# SOC_PMU_Controller.net
KiCad netlist of a schematic drawn in Altium Designer
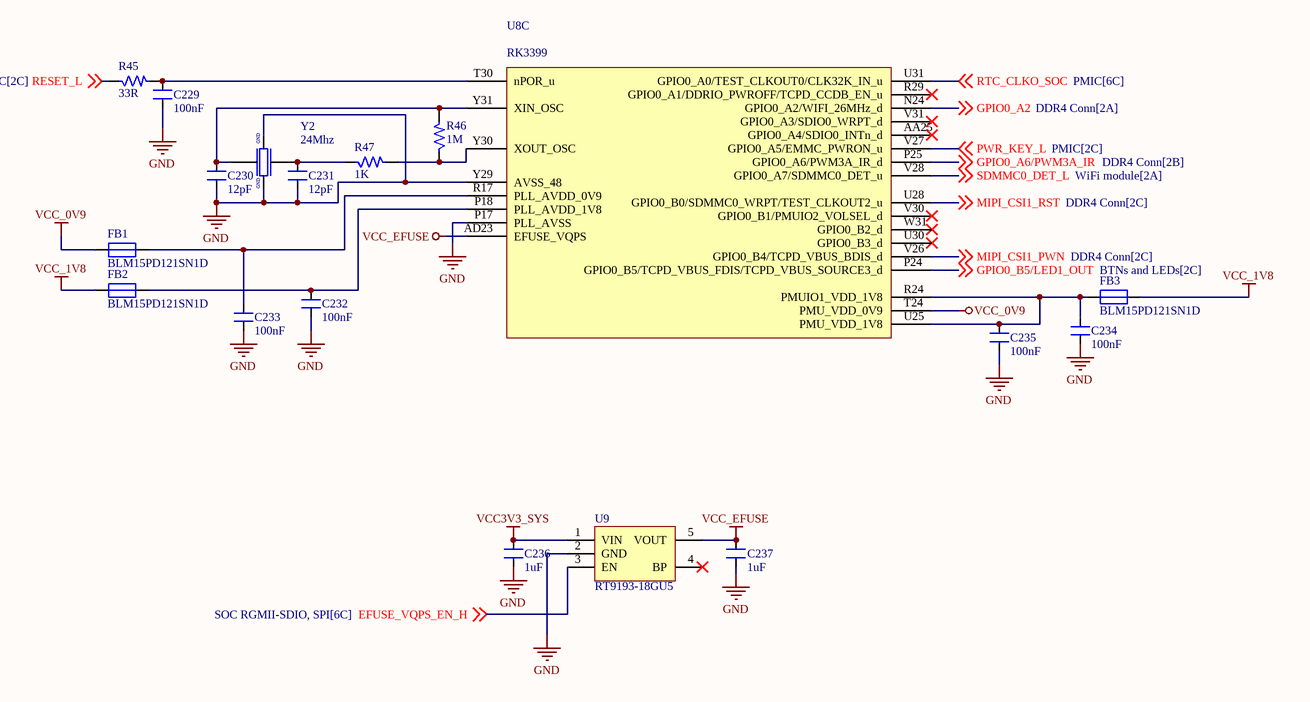
[diagram p0: SOC PMU Controller.SchDoc]

(export (version "E")
  (design (tool "Eeschema 10.0.6"))
  (components
    (comp (ref "C229")
      (value "100nF")
      (footprint "CAP_0201")
      (description "0.1µF ±10% 25V Ceramic Capacitor X5R 0201 (0603 Metric)")
      (fields
        (field (name "MANUFACTURER") "TDK Corporation")
        (field (name "MANUFACTURER PART NUMBER") "C0603X5R1E104K030BB")
      )
      (libsource (lib "RK3399 _Module_Intlib") (part "CAP_100nF-25V-10%-0201"))
    )
    (comp (ref "C230")
      (value "12pF")
      (footprint "CAP_0201")
      (description "12pF ±10% 16V Ceramic Capacitor C0G, NP0 0201 (0603 Metric)")
      (fields
        (field (name "MANUFACTURER") "AVX Corporation")
        (field (name "MANUFACTURER PART NUMBER") "0201YA120KAT2A")
      )
      (libsource (lib "RK3399 _Module_Intlib") (part "CAP_12pF-16V-10%-0201"))
    )
    (comp (ref "C231")
      (value "12pF")
      (footprint "CAP_0201")
      (description "12pF ±10% 16V Ceramic Capacitor C0G, NP0 0201 (0603 Metric)")
      (fields
        (field (name "MANUFACTURER") "AVX Corporation")
        (field (name "MANUFACTURER PART NUMBER") "0201YA120KAT2A")
      )
      (libsource (lib "RK3399 _Module_Intlib") (part "CAP_12pF-16V-10%-0201"))
    )
    (comp (ref "C232")
      (value "100nF")
      (footprint "CAP_0201")
      (description "0.1µF ±10% 25V Ceramic Capacitor X5R 0201 (0603 Metric)")
      (fields
        (field (name "MANUFACTURER") "TDK Corporation")
        (field (name "MANUFACTURER PART NUMBER") "C0603X5R1E104K030BB")
      )
      (libsource (lib "RK3399 _Module_Intlib") (part "CAP_100nF-25V-10%-0201"))
    )
    (comp (ref "C233")
      (value "100nF")
      (footprint "CAP_0201")
      (description "0.1µF ±10% 25V Ceramic Capacitor X5R 0201 (0603 Metric)")
      (fields
        (field (name "MANUFACTURER") "TDK Corporation")
        (field (name "MANUFACTURER PART NUMBER") "C0603X5R1E104K030BB")
      )
      (libsource (lib "RK3399 _Module_Intlib") (part "CAP_100nF-25V-10%-0201"))
    )
    (comp (ref "C234")
      (value "100nF")
      (footprint "CAP_0201")
      (description "0.1µF ±10% 25V Ceramic Capacitor X5R 0201 (0603 Metric)")
      (fields
        (field (name "MANUFACTURER") "TDK Corporation")
        (field (name "MANUFACTURER PART NUMBER") "C0603X5R1E104K030BB")
      )
      (libsource (lib "RK3399 _Module_Intlib") (part "CAP_100nF-25V-10%-0201"))
    )
    (comp (ref "C235")
      (value "100nF")
      (footprint "CAP_0201")
      (description "0.1µF ±10% 25V Ceramic Capacitor X5R 0201 (0603 Metric)")
      (fields
        (field (name "MANUFACTURER") "TDK Corporation")
        (field (name "MANUFACTURER PART NUMBER") "C0603X5R1E104K030BB")
      )
      (libsource (lib "RK3399 _Module_Intlib") (part "CAP_100nF-25V-10%-0201"))
    )
    (comp (ref "C236")
      (value "1uF")
      (footprint "CAP_0201")
      (description "1µF ±20% 16V Ceramic Capacitor X5R 0201 (0603 Metric)")
      (fields
        (field (name "MANUFACTURER") "Samsung Electro-Mechanics")
        (field (name "MANUFACTURER PART NUMBER") "CL03A105MO3NRNH")
      )
      (libsource (lib "RK3399 _Module_Intlib") (part "CAP_1uF-16V-10%-0201"))
    )
    (comp (ref "C237")
      (value "1uF")
      (footprint "CAP_0201")
      (description "1µF ±20% 16V Ceramic Capacitor X5R 0201 (0603 Metric)")
      (fields
        (field (name "MANUFACTURER") "Samsung Electro-Mechanics")
        (field (name "MANUFACTURER PART NUMBER") "CL03A105MO3NRNH")
      )
      (libsource (lib "RK3399 _Module_Intlib") (part "CAP_1uF-16V-10%-0201"))
    )
    (comp (ref "FB1")
      (value "BLM15PD121SN1D")
      (footprint "RES_0402")
      (description "120 Ohms @ 100MHz 1 Power Line Ferrite Bead 0402 (1005 Metric) 1.3A 90mOhm")
      (fields (field (name "MANUFACTURER") "Murata Electronics"))
      (libsource (lib "RK3399 _Module_Schlib") (part "FB_120R-1.3A-100Mhz-0402"))
    )
    (comp (ref "FB2")
      (value "BLM15PD121SN1D")
      (footprint "RES_0402")
      (description "120 Ohms @ 100MHz 1 Power Line Ferrite Bead 0402 (1005 Metric) 1.3A 90mOhm")
      (fields (field (name "MANUFACTURER") "Murata Electronics"))
      (libsource (lib "RK3399 _Module_Schlib") (part "FB_120R-1.3A-100Mhz-0402"))
    )
    (comp (ref "FB3")
      (value "BLM15PD121SN1D")
      (footprint "RES_0402")
      (description "120 Ohms @ 100MHz 1 Power Line Ferrite Bead 0402 (1005 Metric) 1.3A 90mOhm")
      (fields (field (name "MANUFACTURER") "Murata Electronics"))
      (libsource (lib "RK3399 _Module_Schlib") (part "FB_120R-1.3A-100Mhz-0402"))
    )
    (comp (ref "R45")
      (value "33R")
      (footprint "RES_0201")
      (description "33 Ohms ±1% 0.05W, 1/20W Chip Resistor 0201 (0603 Metric) Thick Film")
      (fields
        (field (name "MANUFACTURER") "Yageo")
        (field (name "MANUFACTURER PART NUMBER") "RC0201FR-0733RL")
      )
      (libsource (lib "RK3399 _Module_Intlib") (part "RES_33R-0.05W-1%-0201"))
    )
    (comp (ref "R46")
      (value "1M")
      (footprint "RES_0201")
      (description "1 MOhms ±1% 0.05W, 1/20W Chip Resistor 0201 (0603 Metric) Thick Film")
      (fields
        (field (name "MANUFACTURER") "Yageo")
        (field (name "MANUFACTURER PART NUMBER") "RC0201FR-071ML")
      )
      (libsource (lib "RK3399 _Module_Intlib") (part "RES_1M-0.05W-1%-0201"))
    )
    (comp (ref "R47")
      (value "1K")
      (footprint "RES_0201")
      (description "1 kOhms ±1% 0.05W, 1/20W Chip Resistor 0201 (0603 Metric) Thick Film")
      (fields
        (field (name "MANUFACTURER") "Yageo")
        (field (name "MANUFACTURER PART NUMBER") "RC0201FR-071KL")
      )
      (libsource (lib "RK3399 _Module_Intlib") (part "RES_1K-0.05W-1%-0201"))
    )
    (comp (ref "U8")
      (value "RK3399")
      (footprint "FBGA828_23_826X826")
      (description "RK3399 is a low power, high performance processor for computing, personal mobile.")
      (fields (field (name "MANUFACTURER") "Rockchip"))
      (libsource (lib "RK3399 _Module_Schlib") (part "IC_RK3399-FCBGA828"))
    )
    (comp (ref "U9")
      (value "RT9193-18GU5")
      (footprint "SC70-5")
      (description "Linear Voltage Regulator IC 1 Output 300mA SC-70-5")
      (fields (field (name "MANUFACTURER") "Richtek USA Inc."))
      (libsource (lib "RK3399 _Module_Schlib") (part "REG_1.8V-300mA-5.5V-SC70-5"))
    )
    (comp (ref "Y2")
      (value "24Mhz")
      (footprint "XTAL_ABM8AIG-24.000MHZ-12-2Z-T3")
      (description "24MHz ±20ppm Crystal 12pF 50 Ohms 4-SMD, No Lead")
      (fields
        (field (name "MANUFACTURER") "Abracon LLC")
        (field (name "MANUFACTURER PART NUMBER") "ABM8AIG-24.000MHZ-12-2Z-T3")
      )
      (libsource (lib "RK3399 _Module_Schlib") (part "XTAL_24Mhz-12pF-4-SMD"))
    )
  )
  (nets
    (net (code "1") (name "EFUSE_VQPS_EN_H") (class "Default")
      (node (ref "U9") (pin "3") (pinfunction "EN_3") (pintype "passive"))
    )
    (net (code "2") (name "GND") (class "Default")
      (node (ref "C229") (pin "1") (pinfunction "1_1") (pintype "passive"))
      (node (ref "C230") (pin "1") (pinfunction "1_1") (pintype "passive"))
      (node (ref "C231") (pin "1") (pinfunction "1_1") (pintype "passive"))
      (node (ref "C232") (pin "1") (pinfunction "1_1") (pintype "passive"))
      (node (ref "C233") (pin "1") (pinfunction "1_1") (pintype "passive"))
      (node (ref "C234") (pin "1") (pinfunction "1_1") (pintype "passive"))
      (node (ref "C235") (pin "1") (pinfunction "1_1") (pintype "passive"))
      (node (ref "C236") (pin "1") (pinfunction "1_1") (pintype "passive"))
      (node (ref "C237") (pin "1") (pinfunction "1_1") (pintype "passive"))
      (node (ref "U8") (pin "P17") (pinfunction "PLL_AVSS_P17") (pintype "passive"))
      (node (ref "U8") (pin "Y29") (pinfunction "AVSS_48_Y29") (pintype "passive"))
      (node (ref "U9") (pin "2") (pinfunction "GND_2") (pintype "passive"))
      (node (ref "Y2") (pin "2") (pinfunction "2_2") (pintype "passive"))
      (node (ref "Y2") (pin "4") (pinfunction "4_4") (pintype "passive"))
    )
    (net (code "3") (name "GPIO0_A2") (class "Default")
      (node (ref "U8") (pin "N24") (pinfunction "GPIO0_A2/WIFI_26MHz_d_N24") (pintype "passive"))
    )
    (net (code "4") (name "GPIO0_A6{slash}PWM3A_IR") (class "Default")
      (node (ref "U8") (pin "P25") (pinfunction "GPIO0_A6/PWM3A_IR_d_P25") (pintype "passive"))
    )
    (net (code "5") (name "GPIO0_B5{slash}LED1_OUT") (class "Default")
      (node (ref "U8") (pin "P24") (pinfunction "GPIO0_B5/TCPD_VBUS_FDIS/TCPD_VBUS_SOURCE3_d_P24") (pintype "passive"))
    )
    (net (code "6") (name "MIPI_CSI1_PWN") (class "Default")
      (node (ref "U8") (pin "V26") (pinfunction "GPIO0_B4/TCPD_VBUS_BDIS_d_V26") (pintype "passive"))
    )
    (net (code "7") (name "MIPI_CSI1_RST") (class "Default")
      (node (ref "U8") (pin "U28") (pinfunction "GPIO0_B0/SDMMC0_WRPT/TEST_CLKOUT2_u_U28") (pintype "passive"))
    )
    (net (code "8") (name "Net-(C231-Pad2)") (class "Default")
      (node (ref "C231") (pin "2") (pinfunction "2_2") (pintype "passive"))
      (node (ref "R47") (pin "1") (pinfunction "1_1") (pintype "passive"))
      (node (ref "Y2") (pin "3") (pinfunction "3_3") (pintype "passive"))
    )
    (net (code "9") (name "Net-(U8C-PLL_AVDD_0V9)") (class "Default")
      (node (ref "C233") (pin "2") (pinfunction "2_2") (pintype "passive"))
      (node (ref "FB1") (pin "2") (pinfunction "2_2") (pintype "passive"))
      (node (ref "U8") (pin "R17") (pinfunction "PLL_AVDD_0V9_R17") (pintype "passive"))
    )
    (net (code "10") (name "Net-(U8C-PLL_AVDD_1V8)") (class "Default")
      (node (ref "C232") (pin "2") (pinfunction "2_2") (pintype "passive"))
      (node (ref "FB2") (pin "2") (pinfunction "2_2") (pintype "passive"))
      (node (ref "U8") (pin "P18") (pinfunction "PLL_AVDD_1V8_P18") (pintype "passive"))
    )
    (net (code "11") (name "Net-(U8C-PMUIO1_VDD_1V8)") (class "Default")
      (node (ref "C234") (pin "2") (pinfunction "2_2") (pintype "passive"))
      (node (ref "C235") (pin "2") (pinfunction "2_2") (pintype "passive"))
      (node (ref "FB3") (pin "1") (pinfunction "1_1") (pintype "passive"))
      (node (ref "U8") (pin "R24") (pinfunction "PMUIO1_VDD_1V8_R24") (pintype "passive"))
      (node (ref "U8") (pin "U25") (pinfunction "PMU_VDD_1V8_U25") (pintype "passive"))
    )
    (net (code "12") (name "Net-(U8C-XIN_OSC)") (class "Default")
      (node (ref "C230") (pin "2") (pinfunction "2_2") (pintype "passive"))
      (node (ref "R46") (pin "2") (pinfunction "2_2") (pintype "passive"))
      (node (ref "U8") (pin "Y31") (pinfunction "XIN_OSC_Y31") (pintype "passive"))
      (node (ref "Y2") (pin "1") (pinfunction "1_1") (pintype "passive"))
    )
    (net (code "13") (name "Net-(U8C-XOUT_OSC)") (class "Default")
      (node (ref "R46") (pin "1") (pinfunction "1_1") (pintype "passive"))
      (node (ref "R47") (pin "2") (pinfunction "2_2") (pintype "passive"))
      (node (ref "U8") (pin "Y30") (pinfunction "XOUT_OSC_Y30") (pintype "passive"))
    )
    (net (code "14") (name "Net-(U8C-nPOR_u)") (class "Default")
      (node (ref "C229") (pin "2") (pinfunction "2_2") (pintype "passive"))
      (node (ref "R45") (pin "2") (pinfunction "2_2") (pintype "passive"))
      (node (ref "U8") (pin "T30") (pinfunction "nPOR_u_T30") (pintype "passive"))
    )
    (net (code "15") (name "PWR_KEY_L") (class "Default")
      (node (ref "U8") (pin "V27") (pinfunction "GPIO0_A5/EMMC_PWRON_u_V27") (pintype "passive"))
    )
    (net (code "16") (name "RESET_L") (class "Default")
      (node (ref "R45") (pin "1") (pinfunction "1_1") (pintype "passive"))
    )
    (net (code "17") (name "RTC_CLKO_SOC") (class "Default")
      (node (ref "U8") (pin "U31") (pinfunction "GPIO0_A0/TEST_CLKOUT0/CLK32K_IN_u_U31") (pintype "passive"))
    )
    (net (code "18") (name "SDMMC0_DET_L") (class "Default")
      (node (ref "U8") (pin "V28") (pinfunction "GPIO0_A7/SDMMC0_DET_u_V28") (pintype "passive"))
    )
    (net (code "19") (name "VCC3V3_SYS") (class "Default")
      (node (ref "C236") (pin "2") (pinfunction "2_2") (pintype "passive"))
      (node (ref "U9") (pin "1") (pinfunction "VIN_1") (pintype "passive"))
    )
    (net (code "20") (name "VCC_0V9") (class "Default")
      (node (ref "FB1") (pin "1") (pinfunction "1_1") (pintype "passive"))
      (node (ref "U8") (pin "T24") (pinfunction "PMU_VDD_0V9_T24") (pintype "passive"))
    )
    (net (code "21") (name "VCC_1V8") (class "Default")
      (node (ref "FB2") (pin "1") (pinfunction "1_1") (pintype "passive"))
      (node (ref "FB3") (pin "2") (pinfunction "2_2") (pintype "passive"))
    )
    (net (code "22") (name "VCC_EFUSE") (class "Default")
      (node (ref "C237") (pin "2") (pinfunction "2_2") (pintype "passive"))
      (node (ref "U8") (pin "AD23") (pinfunction "EFUSE_VQPS_AD23") (pintype "passive"))
      (node (ref "U9") (pin "5") (pinfunction "VOUT_5") (pintype "passive"))
    )
    (net (code "23") (name "unconnected-(U8C-GPIO0_A1{slash}DDRIO_PWROFF{slash}TCPD_CCDB_EN_u-PadR29)") (class "Default")
      (node (ref "U8") (pin "R29") (pinfunction "GPIO0_A1/DDRIO_PWROFF/TCPD_CCDB_EN_u_R29") (pintype "passive+no_connect"))
    )
    (net (code "24") (name "unconnected-(U8C-GPIO0_A3{slash}SDIO0_WRPT_d-PadV31)") (class "Default")
      (node (ref "U8") (pin "V31") (pinfunction "GPIO0_A3/SDIO0_WRPT_d_V31") (pintype "passive+no_connect"))
    )
    (net (code "25") (name "unconnected-(U8C-GPIO0_A4{slash}SDIO0_INTn_d-PadAA25)") (class "Default")
      (node (ref "U8") (pin "AA25") (pinfunction "GPIO0_A4/SDIO0_INTn_d_AA25") (pintype "passive+no_connect"))
    )
    (net (code "26") (name "unconnected-(U8C-GPIO0_B1{slash}PMUIO2_VOLSEL_d-PadV30)") (class "Default")
      (node (ref "U8") (pin "V30") (pinfunction "GPIO0_B1/PMUIO2_VOLSEL_d_V30") (pintype "passive+no_connect"))
    )
    (net (code "27") (name "unconnected-(U8C-GPIO0_B2_d-PadW31)") (class "Default")
      (node (ref "U8") (pin "W31") (pinfunction "GPIO0_B2_d_W31") (pintype "passive+no_connect"))
    )
    (net (code "28") (name "unconnected-(U8C-GPIO0_B3_d-PadU30)") (class "Default")
      (node (ref "U8") (pin "U30") (pinfunction "GPIO0_B3_d_U30") (pintype "passive+no_connect"))
    )
    (net (code "29") (name "unconnected-(U9-BP-Pad4)") (class "Default")
      (node (ref "U9") (pin "4") (pinfunction "BP_4") (pintype "passive+no_connect"))
    )
  )
)
